# KeyBaord_V0_1.net
KiCad netlist of a schematic drawn in Altium Designer
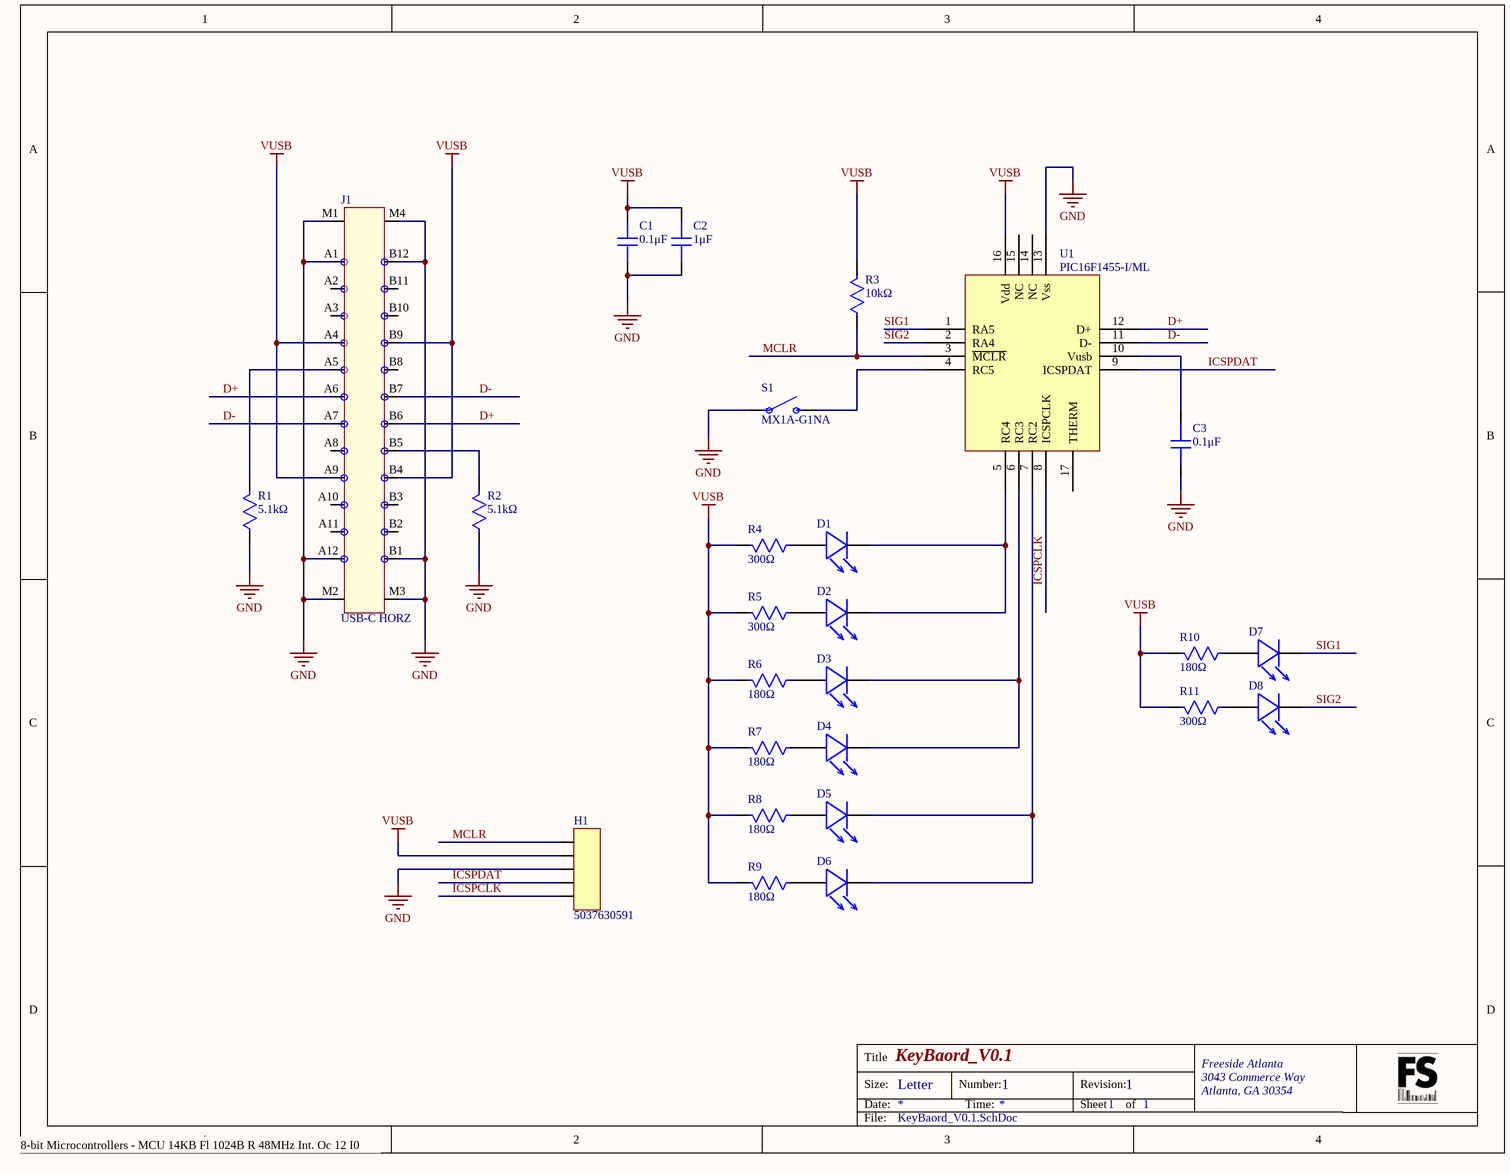
[diagram p0: KeyBaord_V0.1.SchDoc]

(export (version "E")
  (design (tool "Eeschema 10.0.6"))
  (components
    (comp (ref "C1")
      (value "0.1μF")
      (footprint "AVX_MLCC_X7R-0402C")
      (description "MLCC C0G 0402 10V 0.1μF 20%")
      (fields (field (name "MPN") "0402ZC104MAT2A") (field (name "VOLTAGE") "10V"))
      (libsource (lib "KeyBaord_V0.1") (part "0402ZC104MAT2A"))
    )
    (comp (ref "C2")
      (value "1μF")
      (footprint "AVX_MLCC_X7R-0805N")
      (description "MLCC C0G 0805 10V 1μF 20%")
      (fields (field (name "MPN") "0805ZC105MAT2A") (field (name "VOLTAGE") "10V"))
      (libsource (lib "KeyBaord_V0.1") (part "0805ZC105MAT2A"))
    )
    (comp (ref "C3")
      (value "0.1μF")
      (footprint "AVX_MLCC_X7R-0402C")
      (description "MLCC C0G 0402 10V 0.1μF 20%")
      (fields (field (name "MPN") "0402ZC104MAT2A") (field (name "VOLTAGE") "10V"))
      (libsource (lib "KeyBaord_V0.1") (part "0402ZC104MAT2A"))
    )
    (comp (ref "D1")
      (value "0603 Red")
      (footprint "150060RS55040")
      (description "Standard LEDs - SMD WL-SMCD SMD MonoChip 0603 Red 632nm")
      (fields (field (name "MPN") "150060RS55040"))
      (libsource (lib "KeyBaord_V0.1") (part "150060RS55040"))
    )
    (comp (ref "D2")
      (value "0603 Red")
      (footprint "150060RS55040")
      (description "Standard LEDs - SMD WL-SMCD SMD MonoChip 0603 Red 632nm")
      (fields (field (name "MPN") "150060RS55040"))
      (libsource (lib "KeyBaord_V0.1") (part "150060RS55040"))
    )
    (comp (ref "D3")
      (value "0603 Green")
      (footprint "150060GS55040")
      (description "Standard LEDs - SMD WL-SMCD SMD Mono SMD 0603 Green 520nm")
      (fields (field (name "MPN") "150060GS55040"))
      (libsource (lib "KeyBaord_V0.1") (part "150060GS55040"))
    )
    (comp (ref "D4")
      (value "0603 Green")
      (footprint "150060GS55040")
      (description "Standard LEDs - SMD WL-SMCD SMD Mono SMD 0603 Green 520nm")
      (fields (field (name "MPN") "150060GS55040"))
      (libsource (lib "KeyBaord_V0.1") (part "150060GS55040"))
    )
    (comp (ref "D5")
      (value "0603 Blue")
      (footprint "150060BS55040")
      (description "Standard LEDs - SMD WL-SMCD SMD Mono SMD 0603 Blue 465nm")
      (fields (field (name "MPN") "150060BS55040"))
      (libsource (lib "KeyBaord_V0.1") (part "150060BS55040"))
    )
    (comp (ref "D6")
      (value "0603 Blue")
      (footprint "150060BS55040")
      (description "Standard LEDs - SMD WL-SMCD SMD Mono SMD 0603 Blue 465nm")
      (fields (field (name "MPN") "150060BS55040"))
      (libsource (lib "KeyBaord_V0.1") (part "150060BS55040"))
    )
    (comp (ref "D7")
      (value "0603 Blue")
      (footprint "150060BS55040")
      (description "Standard LEDs - SMD WL-SMCD SMD Mono SMD 0603 Blue 465nm")
      (fields (field (name "MPN") "150060BS55040"))
      (libsource (lib "KeyBaord_V0.1") (part "150060BS55040"))
    )
    (comp (ref "D8")
      (value "0603 Red")
      (footprint "150060RS55040")
      (description "Standard LEDs - SMD WL-SMCD SMD MonoChip 0603 Red 632nm")
      (fields (field (name "MPN") "150060RS55040"))
      (libsource (lib "KeyBaord_V0.1") (part "150060RS55040"))
    )
    (comp (ref "H1")
      (value "5037630591")
      (footprint "5037630591")
      (description "Headers & Wire Housings 1MM PicoLock SMT HDR RA POD SIDELOCK 5CKT")
      (libsource (lib "KeyBaord_V0.1") (part "5037630591"))
    )
    (comp (ref "J1")
      (value "USB-C HORZ")
      (footprint "Molex_USB-C HORZ")
      (description "CONN RCP USB3.1 TYPEC 24P SMD RA")
      (fields (field (name "MPN") "1054500101") (field (name "DIGI-KEY PART NUMBER") "WM12856CT-ND"))
      (libsource (lib "KeyBaord_V0.1") (part "USB-C_HORZ"))
    )
    (comp (ref "R1")
      (value "5.1kΩ")
      (footprint "0402_2GE")
      (description "Thick Film Resistors - SMD 0402 5.1Kohms 5% AEC-Q200")
      (fields (field (name "MPN") "ERJ-2GEJ512X") (field (name "TOLERANCE") "5%"))
      (libsource (lib "KeyBaord_V0.1") (part "ERJ-2GEJ512X"))
    )
    (comp (ref "R2")
      (value "5.1kΩ")
      (footprint "0402_2GE")
      (description "Thick Film Resistors - SMD 0402 5.1Kohms 5% AEC-Q200")
      (fields (field (name "MPN") "ERJ-2GEJ512X") (field (name "TOLERANCE") "5%"))
      (libsource (lib "KeyBaord_V0.1") (part "ERJ-2GEJ512X"))
    )
    (comp (ref "R3")
      (value "10kΩ")
      (footprint "0402_2GE")
      (description "Thick Film Resistors - SMD 0402 10Kohms 5% AEC-Q200")
      (fields (field (name "MPN") "ERJ-2GEJ103X") (field (name "TOLERANCE") "5%"))
      (libsource (lib "KeyBaord_V0.1") (part "ERJ-2GEJ103X"))
    )
    (comp (ref "R4")
      (value "300Ω")
      (footprint "0402_2GE")
      (description "Thick Film Resistors - SMD 0402 300ohms 5% AEC-Q200")
      (fields (field (name "MPN") "ERJ-2GEJ301X") (field (name "TOLERANCE") "5%"))
      (libsource (lib "KeyBaord_V0.1") (part "ERJ-2GEJ301X"))
    )
    (comp (ref "R5")
      (value "300Ω")
      (footprint "0402_2GE")
      (description "Thick Film Resistors - SMD 0402 300ohms 5% AEC-Q200")
      (fields (field (name "MPN") "ERJ-2GEJ301X") (field (name "TOLERANCE") "5%"))
      (libsource (lib "KeyBaord_V0.1") (part "ERJ-2GEJ301X"))
    )
    (comp (ref "R6")
      (value "180Ω")
      (footprint "0402_2GE")
      (description "Thick Film Resistors - SMD 0402 180ohms 5% AEC-Q200")
      (fields (field (name "MPN") "ERJ-2GEJ181X") (field (name "TOLERANCE") "5%"))
      (libsource (lib "KeyBaord_V0.1") (part "ERJ-2GEJ181X"))
    )
    (comp (ref "R7")
      (value "180Ω")
      (footprint "0402_2GE")
      (description "Thick Film Resistors - SMD 0402 180ohms 5% AEC-Q200")
      (fields (field (name "MPN") "ERJ-2GEJ181X") (field (name "TOLERANCE") "5%"))
      (libsource (lib "KeyBaord_V0.1") (part "ERJ-2GEJ181X"))
    )
    (comp (ref "R8")
      (value "180Ω")
      (footprint "0402_2GE")
      (description "Thick Film Resistors - SMD 0402 180ohms 5% AEC-Q200")
      (fields (field (name "MPN") "ERJ-2GEJ181X") (field (name "TOLERANCE") "5%"))
      (libsource (lib "KeyBaord_V0.1") (part "ERJ-2GEJ181X"))
    )
    (comp (ref "R9")
      (value "180Ω")
      (footprint "0402_2GE")
      (description "Thick Film Resistors - SMD 0402 180ohms 5% AEC-Q200")
      (fields (field (name "MPN") "ERJ-2GEJ181X") (field (name "TOLERANCE") "5%"))
      (libsource (lib "KeyBaord_V0.1") (part "ERJ-2GEJ181X"))
    )
    (comp (ref "R10")
      (value "180Ω")
      (footprint "0402_2GE")
      (description "Thick Film Resistors - SMD 0402 180ohms 5% AEC-Q200")
      (fields (field (name "MPN") "ERJ-2GEJ181X") (field (name "TOLERANCE") "5%"))
      (libsource (lib "KeyBaord_V0.1") (part "ERJ-2GEJ181X"))
    )
    (comp (ref "R11")
      (value "300Ω")
      (footprint "0402_2GE")
      (description "Thick Film Resistors - SMD 0402 300ohms 5% AEC-Q200")
      (fields (field (name "MPN") "ERJ-2GEJ301X") (field (name "TOLERANCE") "5%"))
      (libsource (lib "KeyBaord_V0.1") (part "ERJ-2GEJ301X"))
    )
    (comp (ref "S1")
      (value "MX1A-G1NA")
      (footprint "MX1A-G1NA")
      (libsource (lib "KeyBaord_V0.1") (part "MX1A-G1NA"))
    )
    (comp (ref "U1")
      (value "PIC16F1455-I/ML")
      (footprint "PIC16F1455-I/ML")
      (description "8-bit Microcontrollers - MCU 14KB Fl 1024B R 48MHz Int. Oc 12 I0")
      (libsource (lib "KeyBaord_V0.1") (part "PIC16F1455-I/ML"))
    )
  )
  (nets
    (net (code "1") (name "/D+") (class "Default")
      (node (ref "J1") (pin "A6") (pintype "passive"))
      (node (ref "J1") (pin "B6") (pintype "passive"))
      (node (ref "U1") (pin "12") (pinfunction "D+_12") (pintype "passive"))
    )
    (net (code "2") (name "/D-") (class "Default")
      (node (ref "J1") (pin "A7") (pintype "passive"))
      (node (ref "J1") (pin "B7") (pintype "passive"))
      (node (ref "U1") (pin "11") (pinfunction "D-_11") (pintype "passive"))
    )
    (net (code "3") (name "/ICSPCLK") (class "Default")
      (node (ref "H1") (pin "1") (pinfunction "1_1") (pintype "passive"))
      (node (ref "U1") (pin "8") (pinfunction "ICSPCLK_8") (pintype "passive"))
    )
    (net (code "4") (name "/ICSPDAT") (class "Default")
      (node (ref "H1") (pin "2") (pinfunction "2_2") (pintype "passive"))
      (node (ref "U1") (pin "9") (pinfunction "ICSPDAT_9") (pintype "passive"))
    )
    (net (code "5") (name "/MCLR") (class "Default")
      (node (ref "H1") (pin "5") (pinfunction "5_5") (pintype "passive"))
      (node (ref "R3") (pin "2") (pinfunction "2_2") (pintype "passive"))
      (node (ref "U1") (pin "3") (pinfunction "~{MCLR}_3") (pintype "passive"))
    )
    (net (code "6") (name "/SIG1") (class "Default")
      (node (ref "D7") (pin "C") (pinfunction "C_C") (pintype "passive"))
      (node (ref "U1") (pin "1") (pinfunction "RA5_1") (pintype "passive"))
    )
    (net (code "7") (name "/SIG2") (class "Default")
      (node (ref "D8") (pin "C") (pinfunction "C_C") (pintype "passive"))
      (node (ref "U1") (pin "2") (pinfunction "RA4_2") (pintype "passive"))
    )
    (net (code "8") (name "GND") (class "Default")
      (node (ref "C1") (pin "1") (pinfunction "1_1") (pintype "passive"))
      (node (ref "C2") (pin "1") (pinfunction "1_1") (pintype "passive"))
      (node (ref "C3") (pin "1") (pinfunction "1_1") (pintype "passive"))
      (node (ref "H1") (pin "3") (pinfunction "3_3") (pintype "passive"))
      (node (ref "J1") (pin "A1") (pintype "passive"))
      (node (ref "J1") (pin "A12") (pintype "passive"))
      (node (ref "J1") (pin "B1") (pintype "passive"))
      (node (ref "J1") (pin "B12") (pintype "passive"))
      (node (ref "J1") (pin "M1") (pintype "passive"))
      (node (ref "J1") (pin "M2") (pintype "passive"))
      (node (ref "J1") (pin "M3") (pintype "passive"))
      (node (ref "J1") (pin "M4") (pintype "passive"))
      (node (ref "R1") (pin "2") (pinfunction "2_2") (pintype "passive"))
      (node (ref "R2") (pin "2") (pinfunction "2_2") (pintype "passive"))
      (node (ref "S1") (pin "1") (pinfunction "1_1") (pintype "passive"))
      (node (ref "U1") (pin "13") (pinfunction "Vss_13") (pintype "passive"))
    )
    (net (code "9") (name "Net-(D1-PadA)") (class "Default")
      (node (ref "D1") (pin "A") (pinfunction "A_A") (pintype "passive"))
      (node (ref "R4") (pin "2") (pinfunction "2_2") (pintype "passive"))
    )
    (net (code "10") (name "Net-(D2-PadA)") (class "Default")
      (node (ref "D2") (pin "A") (pinfunction "A_A") (pintype "passive"))
      (node (ref "R5") (pin "2") (pinfunction "2_2") (pintype "passive"))
    )
    (net (code "11") (name "Net-(D3-PadA)") (class "Default")
      (node (ref "D3") (pin "A") (pinfunction "A_A") (pintype "passive"))
      (node (ref "R6") (pin "2") (pinfunction "2_2") (pintype "passive"))
    )
    (net (code "12") (name "Net-(D4-PadA)") (class "Default")
      (node (ref "D4") (pin "A") (pinfunction "A_A") (pintype "passive"))
      (node (ref "R7") (pin "2") (pinfunction "2_2") (pintype "passive"))
    )
    (net (code "13") (name "Net-(D5-PadA)") (class "Default")
      (node (ref "D5") (pin "A") (pinfunction "A_A") (pintype "passive"))
      (node (ref "R8") (pin "2") (pinfunction "2_2") (pintype "passive"))
    )
    (net (code "14") (name "Net-(D6-PadA)") (class "Default")
      (node (ref "D6") (pin "A") (pinfunction "A_A") (pintype "passive"))
      (node (ref "R9") (pin "2") (pinfunction "2_2") (pintype "passive"))
    )
    (net (code "15") (name "Net-(D7-PadA)") (class "Default")
      (node (ref "D7") (pin "A") (pinfunction "A_A") (pintype "passive"))
      (node (ref "R10") (pin "2") (pinfunction "2_2") (pintype "passive"))
    )
    (net (code "16") (name "Net-(D8-PadA)") (class "Default")
      (node (ref "D8") (pin "A") (pinfunction "A_A") (pintype "passive"))
      (node (ref "R11") (pin "2") (pinfunction "2_2") (pintype "passive"))
    )
    (net (code "17") (name "Net-(J1-PadA5)") (class "Default")
      (node (ref "J1") (pin "A5") (pintype "passive"))
      (node (ref "R1") (pin "1") (pinfunction "1_1") (pintype "passive"))
    )
    (net (code "18") (name "Net-(J1-PadB5)") (class "Default")
      (node (ref "J1") (pin "B5") (pintype "passive"))
      (node (ref "R2") (pin "1") (pinfunction "1_1") (pintype "passive"))
    )
    (net (code "19") (name "Net-(U1-RC2)") (class "Default")
      (node (ref "D5") (pin "C") (pinfunction "C_C") (pintype "passive"))
      (node (ref "D6") (pin "C") (pinfunction "C_C") (pintype "passive"))
      (node (ref "U1") (pin "7") (pinfunction "RC2_7") (pintype "passive"))
    )
    (net (code "20") (name "Net-(U1-RC3)") (class "Default")
      (node (ref "D3") (pin "C") (pinfunction "C_C") (pintype "passive"))
      (node (ref "D4") (pin "C") (pinfunction "C_C") (pintype "passive"))
      (node (ref "U1") (pin "6") (pinfunction "RC3_6") (pintype "passive"))
    )
    (net (code "21") (name "Net-(U1-RC4)") (class "Default")
      (node (ref "D1") (pin "C") (pinfunction "C_C") (pintype "passive"))
      (node (ref "D2") (pin "C") (pinfunction "C_C") (pintype "passive"))
      (node (ref "U1") (pin "5") (pinfunction "RC4_5") (pintype "passive"))
    )
    (net (code "22") (name "Net-(U1-RC5)") (class "Default")
      (node (ref "S1") (pin "2") (pinfunction "2_2") (pintype "passive"))
      (node (ref "U1") (pin "4") (pinfunction "RC5_4") (pintype "passive"))
    )
    (net (code "23") (name "Net-(U1-Vusb)") (class "Default")
      (node (ref "C3") (pin "2") (pinfunction "2_2") (pintype "passive"))
      (node (ref "U1") (pin "10") (pinfunction "Vusb_10") (pintype "passive"))
    )
    (net (code "24") (name "VUSB") (class "Default")
      (node (ref "C1") (pin "2") (pinfunction "2_2") (pintype "passive"))
      (node (ref "C2") (pin "2") (pinfunction "2_2") (pintype "passive"))
      (node (ref "H1") (pin "4") (pinfunction "4_4") (pintype "passive"))
      (node (ref "J1") (pin "A4") (pintype "passive"))
      (node (ref "J1") (pin "A9") (pintype "passive"))
      (node (ref "J1") (pin "B4") (pintype "passive"))
      (node (ref "J1") (pin "B9") (pintype "passive"))
      (node (ref "R10") (pin "1") (pinfunction "1_1") (pintype "passive"))
      (node (ref "R11") (pin "1") (pinfunction "1_1") (pintype "passive"))
      (node (ref "R3") (pin "1") (pinfunction "1_1") (pintype "passive"))
      (node (ref "R4") (pin "1") (pinfunction "1_1") (pintype "passive"))
      (node (ref "R5") (pin "1") (pinfunction "1_1") (pintype "passive"))
      (node (ref "R6") (pin "1") (pinfunction "1_1") (pintype "passive"))
      (node (ref "R7") (pin "1") (pinfunction "1_1") (pintype "passive"))
      (node (ref "R8") (pin "1") (pinfunction "1_1") (pintype "passive"))
      (node (ref "R9") (pin "1") (pinfunction "1_1") (pintype "passive"))
      (node (ref "U1") (pin "16") (pinfunction "Vdd_16") (pintype "passive"))
    )
    (net (code "25") (name "unconnected-(J1-PadA2)") (class "Default")
      (node (ref "J1") (pin "A2") (pintype "passive"))
    )
    (net (code "26") (name "unconnected-(J1-PadA3)") (class "Default")
      (node (ref "J1") (pin "A3") (pintype "passive"))
    )
    (net (code "27") (name "unconnected-(J1-PadA8)") (class "Default")
      (node (ref "J1") (pin "A8") (pintype "passive"))
    )
    (net (code "28") (name "unconnected-(J1-PadA10)") (class "Default")
      (node (ref "J1") (pin "A10") (pintype "passive"))
    )
    (net (code "29") (name "unconnected-(J1-PadA11)") (class "Default")
      (node (ref "J1") (pin "A11") (pintype "passive"))
    )
    (net (code "30") (name "unconnected-(J1-PadB2)") (class "Default")
      (node (ref "J1") (pin "B2") (pintype "passive"))
    )
    (net (code "31") (name "unconnected-(J1-PadB3)") (class "Default")
      (node (ref "J1") (pin "B3") (pintype "passive"))
    )
    (net (code "32") (name "unconnected-(J1-PadB8)") (class "Default")
      (node (ref "J1") (pin "B8") (pintype "passive"))
    )
    (net (code "33") (name "unconnected-(J1-PadB10)") (class "Default")
      (node (ref "J1") (pin "B10") (pintype "passive"))
    )
    (net (code "34") (name "unconnected-(J1-PadB11)") (class "Default")
      (node (ref "J1") (pin "B11") (pintype "passive"))
    )
    (net (code "35") (name "unconnected-(U1-NC-Pad14)") (class "Default")
      (node (ref "U1") (pin "14") (pinfunction "NC_14") (pintype "passive"))
    )
    (net (code "36") (name "unconnected-(U1-NC-Pad15)") (class "Default")
      (node (ref "U1") (pin "15") (pinfunction "NC_15") (pintype "passive"))
    )
    (net (code "37") (name "unconnected-(U1-THERM-Pad17)") (class "Default")
      (node (ref "U1") (pin "17") (pinfunction "THERM_17") (pintype "passive"))
    )
  )
)
